# PowerReplayUSB.net
KiCad netlist of a schematic drawn in EAGLE
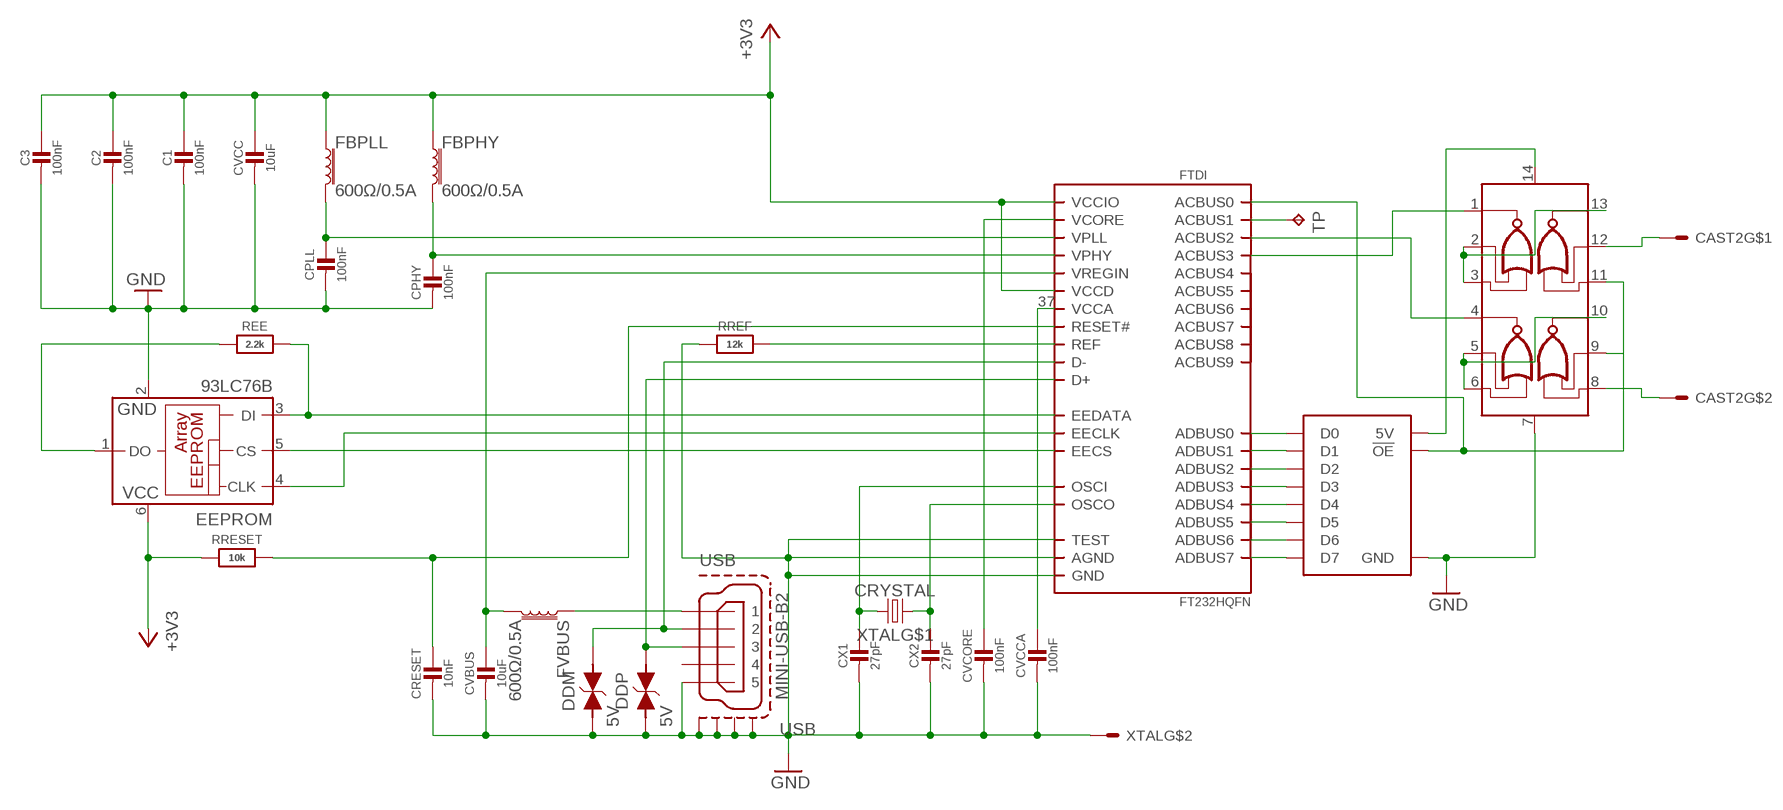
[diagram p0: schematic, sheet 1]

(export (version "E")
  (design (tool "Eeschema 10.0.6"))
  (components
    (comp (ref "C1")
      (value "100nF")
      (footprint "eagle-import:0603")
      (libsource (lib "eagle-import") (part "CAPACITOR0603"))
    )
    (comp (ref "C2")
      (value "100nF")
      (footprint "eagle-import:0603")
      (libsource (lib "eagle-import") (part "CAPACITOR0603"))
    )
    (comp (ref "C3")
      (value "100nF")
      (footprint "eagle-import:0603")
      (libsource (lib "eagle-import") (part "CAPACITOR0603"))
    )
    (comp (ref "CAST1")
      (value "BUFFER-CASTELLATION")
      (footprint "eagle-import:BUFFER-CASTELLATION")
      (libsource (lib "eagle-import") (part "BUFFER-CASTELLATION"))
    )
    (comp (ref "CAST2")
      (value "PLA-CASTELLATION")
      (footprint "eagle-import:PLA-CASTELLATION")
      (libsource (lib "eagle-import") (part "PLA-CASTELLATION"))
    )
    (comp (ref "CPHY")
      (value "100nF")
      (footprint "eagle-import:0603")
      (libsource (lib "eagle-import") (part "CAPACITOR0603"))
    )
    (comp (ref "CPLL")
      (value "100nF")
      (footprint "eagle-import:0603")
      (libsource (lib "eagle-import") (part "CAPACITOR0603"))
    )
    (comp (ref "CRESET")
      (value "10nF")
      (footprint "eagle-import:0603")
      (libsource (lib "eagle-import") (part "CAPACITOR0603"))
    )
    (comp (ref "CVBUS")
      (value "10uF")
      (footprint "eagle-import:1206")
      (libsource (lib "eagle-import") (part "CAPACITOR1206"))
    )
    (comp (ref "CVCC")
      (value "10uF")
      (footprint "eagle-import:1206")
      (libsource (lib "eagle-import") (part "CAPACITOR1206"))
    )
    (comp (ref "CVCCA")
      (value "100nF")
      (footprint "eagle-import:0603")
      (libsource (lib "eagle-import") (part "CAPACITOR0603"))
    )
    (comp (ref "CVCORE")
      (value "100nF")
      (footprint "eagle-import:0603")
      (libsource (lib "eagle-import") (part "CAPACITOR0603"))
    )
    (comp (ref "CX1")
      (value "27pF")
      (footprint "eagle-import:0402")
      (libsource (lib "eagle-import") (part "CAPACITOR0402"))
    )
    (comp (ref "CX2")
      (value "27pF")
      (footprint "eagle-import:0402")
      (libsource (lib "eagle-import") (part "CAPACITOR0402"))
    )
    (comp (ref "DDM")
      (value "5V")
      (footprint "eagle-import:WE-VE_0603")
      (libsource (lib "eagle-import") (part "WE-VE_0603_82356050050"))
    )
    (comp (ref "DDP")
      (value "5V")
      (footprint "eagle-import:WE-VE_0603")
      (libsource (lib "eagle-import") (part "WE-VE_0603_82356050050"))
    )
    (comp (ref "EEPROM")
      (value "93LC76B")
      (footprint "eagle-import:SOT23-6")
      (fields (field (name "MF") "MICROCHIP") (field (name "MPN") "93LC76BT-I/OT"))
      (libsource (lib "eagle-import") (part "9376?BLC"))
    )
    (comp (ref "FBPHY")
      (value "600Ω/0.5A")
      (footprint "eagle-import:0603")
      (libsource (lib "eagle-import") (part "FERRITE_BEAD-0603"))
    )
    (comp (ref "FBPLL")
      (value "600Ω/0.5A")
      (footprint "eagle-import:0603")
      (libsource (lib "eagle-import") (part "FERRITE_BEAD-0603"))
    )
    (comp (ref "FTDI")
      (value "FT232HQFN")
      (footprint "eagle-import:QFN48_8MM")
      (libsource (lib "eagle-import") (part "FT232HQFN"))
    )
    (comp (ref "FVBUS")
      (value "600Ω/0.5A")
      (footprint "eagle-import:0603")
      (libsource (lib "eagle-import") (part "FERRITE_BEAD-0603"))
    )
    (comp (ref "GATES")
      (value "7402TSSOP14")
      (footprint "eagle-import:TSSOP14-RU")
      (libsource (lib "eagle-import") (part "7402TSSOP14"))
    )
    (comp (ref "REE")
      (value "2.2k")
      (footprint "eagle-import:0603")
      (libsource (lib "eagle-import") (part "RESISTOR0603"))
    )
    (comp (ref "RREF")
      (value "12k")
      (footprint "eagle-import:0603")
      (libsource (lib "eagle-import") (part "RESISTOR0603"))
    )
    (comp (ref "RRESET")
      (value "10k")
      (footprint "eagle-import:0603")
      (libsource (lib "eagle-import") (part "RESISTOR0603"))
    )
    (comp (ref "TP") (value "TP") (footprint "eagle-import:TP") (libsource (lib "eagle-import") (part "TP")))
    (comp (ref "USB")
      (value "MINI-USB-B2")
      (footprint "eagle-import:MINI-USB-B-2")
      (libsource (lib "eagle-import") (part "MINI-USB-B2"))
    )
    (comp (ref "XTAL")
      (value "CRYSTAL")
      (footprint "eagle-import:SMD3225-4P")
      (libsource (lib "eagle-import") (part "CRYSTAL"))
    )
  )
  (nets
    (net (code "1") (name "+3V3") (class "Default")
      (node (ref "C1") (pin "1") (pinfunction "1_1") (pintype "passive"))
      (node (ref "C2") (pin "1") (pinfunction "1_1") (pintype "passive"))
      (node (ref "C3") (pin "1") (pinfunction "1_1") (pintype "passive"))
      (node (ref "CVCC") (pin "1") (pinfunction "1_1") (pintype "passive"))
      (node (ref "EEPROM") (pin "6") (pinfunction "VCC_6") (pintype "power_in"))
      (node (ref "FBPHY") (pin "1") (pinfunction "1_1") (pintype "passive"))
      (node (ref "FBPLL") (pin "1") (pinfunction "1_1") (pintype "passive"))
      (node (ref "FTDI") (pin "12") (pinfunction "VCCIO_12") (pintype "bidirectional"))
      (node (ref "FTDI") (pin "24") (pinfunction "VCCIO_24") (pintype "bidirectional"))
      (node (ref "FTDI") (pin "39") (pinfunction "VCCD_39") (pintype "bidirectional"))
      (node (ref "FTDI") (pin "46") (pinfunction "VCCIO_46") (pintype "bidirectional"))
      (node (ref "RRESET") (pin "1") (pinfunction "1_1") (pintype "passive"))
    )
    (net (code "2") (name "GND") (class "Default")
      (node (ref "C1") (pin "2") (pinfunction "2_2") (pintype "passive"))
      (node (ref "C2") (pin "2") (pinfunction "2_2") (pintype "passive"))
      (node (ref "C3") (pin "2") (pinfunction "2_2") (pintype "passive"))
      (node (ref "CAST1") (pin "P$9") (pinfunction "GND_P$9") (pintype "input"))
      (node (ref "CPHY") (pin "2") (pinfunction "2_2") (pintype "passive"))
      (node (ref "CPLL") (pin "2") (pinfunction "2_2") (pintype "passive"))
      (node (ref "CRESET") (pin "2") (pinfunction "2_2") (pintype "passive"))
      (node (ref "CVBUS") (pin "2") (pinfunction "2_2") (pintype "passive"))
      (node (ref "CVCC") (pin "2") (pinfunction "2_2") (pintype "passive"))
      (node (ref "CVCCA") (pin "2") (pinfunction "2_2") (pintype "passive"))
      (node (ref "CVCORE") (pin "2") (pinfunction "2_2") (pintype "passive"))
      (node (ref "CX1") (pin "2") (pinfunction "2_2") (pintype "passive"))
      (node (ref "CX2") (pin "2") (pinfunction "2_2") (pintype "passive"))
      (node (ref "DDM") (pin "2") (pinfunction "2_2") (pintype "passive"))
      (node (ref "DDP") (pin "2") (pinfunction "2_2") (pintype "passive"))
      (node (ref "EEPROM") (pin "2") (pinfunction "GND_2") (pintype "power_in"))
      (node (ref "FTDI") (pin "10") (pinfunction "GND_10") (pintype "bidirectional"))
      (node (ref "FTDI") (pin "11") (pinfunction "GND_11") (pintype "bidirectional"))
      (node (ref "FTDI") (pin "22") (pinfunction "GND_22") (pintype "bidirectional"))
      (node (ref "FTDI") (pin "23") (pinfunction "GND_23") (pintype "bidirectional"))
      (node (ref "FTDI") (pin "35") (pinfunction "GND_35") (pintype "bidirectional"))
      (node (ref "FTDI") (pin "36") (pinfunction "GND_36") (pintype "bidirectional"))
      (node (ref "FTDI") (pin "4") (pinfunction "AGND_4") (pintype "bidirectional"))
      (node (ref "FTDI") (pin "41") (pinfunction "AGND_41") (pintype "bidirectional"))
      (node (ref "FTDI") (pin "42") (pinfunction "TEST_42") (pintype "bidirectional"))
      (node (ref "FTDI") (pin "47") (pinfunction "GND_47") (pintype "bidirectional"))
      (node (ref "FTDI") (pin "48") (pinfunction "GND_48") (pintype "bidirectional"))
      (node (ref "FTDI") (pin "9") (pinfunction "AGND_9") (pintype "bidirectional"))
      (node (ref "FTDI") (pin "THERMAL") (pinfunction "GND_THERMAL") (pintype "bidirectional"))
      (node (ref "GATES") (pin "7") (pinfunction "P$7_7") (pintype "bidirectional"))
      (node (ref "RREF") (pin "1") (pinfunction "1_1") (pintype "passive"))
      (node (ref "USB") (pin "P$5") (pinfunction "5_P$5") (pintype "input"))
      (node (ref "USB") (pin "P$6") (pinfunction "S1_P$6") (pintype "passive"))
      (node (ref "USB") (pin "P$7") (pinfunction "S2_P$7") (pintype "passive"))
      (node (ref "USB") (pin "P$8") (pinfunction "S3_P$8") (pintype "passive"))
      (node (ref "USB") (pin "P$9") (pinfunction "S4_P$9") (pintype "passive"))
      (node (ref "XTAL") (pin "P$2") (pinfunction "S_P$2") (pintype "passive"))
      (node (ref "XTAL") (pin "P$4") (pinfunction "S_P$4") (pintype "passive"))
    )
    (net (code "3") (name "Net-(CAST1-5V)") (class "Default")
      (node (ref "CAST1") (pin "P$11") (pinfunction "5V_P$11") (pintype "input"))
      (node (ref "GATES") (pin "14") (pinfunction "P$14_14") (pintype "bidirectional"))
    )
    (net (code "4") (name "Net-(CAST1-D0)") (class "Default")
      (node (ref "CAST1") (pin "P$1") (pinfunction "D0_P$1") (pintype "input"))
      (node (ref "FTDI") (pin "13") (pinfunction "ADBUS0_13") (pintype "bidirectional"))
    )
    (net (code "5") (name "Net-(CAST1-D1)") (class "Default")
      (node (ref "CAST1") (pin "P$2") (pinfunction "D1_P$2") (pintype "input"))
      (node (ref "FTDI") (pin "14") (pinfunction "ADBUS1_14") (pintype "bidirectional"))
    )
    (net (code "6") (name "Net-(CAST1-D2)") (class "Default")
      (node (ref "CAST1") (pin "P$3") (pinfunction "D2_P$3") (pintype "input"))
      (node (ref "FTDI") (pin "15") (pinfunction "ADBUS2_15") (pintype "bidirectional"))
    )
    (net (code "7") (name "Net-(CAST1-D3)") (class "Default")
      (node (ref "CAST1") (pin "P$4") (pinfunction "D3_P$4") (pintype "input"))
      (node (ref "FTDI") (pin "16") (pinfunction "ADBUS3_16") (pintype "bidirectional"))
    )
    (net (code "8") (name "Net-(CAST1-D4)") (class "Default")
      (node (ref "CAST1") (pin "P$5") (pinfunction "D4_P$5") (pintype "input"))
      (node (ref "FTDI") (pin "17") (pinfunction "ADBUS4_17") (pintype "bidirectional"))
    )
    (net (code "9") (name "Net-(CAST1-D5)") (class "Default")
      (node (ref "CAST1") (pin "P$6") (pinfunction "D5_P$6") (pintype "input"))
      (node (ref "FTDI") (pin "18") (pinfunction "ADBUS5_18") (pintype "bidirectional"))
    )
    (net (code "10") (name "Net-(CAST1-D6)") (class "Default")
      (node (ref "CAST1") (pin "P$7") (pinfunction "D6_P$7") (pintype "input"))
      (node (ref "FTDI") (pin "19") (pinfunction "ADBUS6_19") (pintype "bidirectional"))
    )
    (net (code "11") (name "Net-(CAST1-D7)") (class "Default")
      (node (ref "CAST1") (pin "P$8") (pinfunction "D7_P$8") (pintype "input"))
      (node (ref "FTDI") (pin "20") (pinfunction "ADBUS7_20") (pintype "bidirectional"))
    )
    (net (code "12") (name "Net-(CAST1-~{OE})") (class "Default")
      (node (ref "CAST1") (pin "P$10") (pinfunction "~{OE}_P$10") (pintype "input"))
      (node (ref "FTDI") (pin "21") (pinfunction "ACBUS0_21") (pintype "bidirectional"))
      (node (ref "GATES") (pin "11") (pinfunction "P$11_11") (pintype "bidirectional"))
      (node (ref "GATES") (pin "9") (pinfunction "P$9_9") (pintype "bidirectional"))
    )
    (net (code "13") (name "Net-(CAST2A-S)") (class "Default")
      (node (ref "CAST2") (pin "P$1") (pinfunction "S_P$1") (pintype "passive"))
      (node (ref "GATES") (pin "12") (pinfunction "P$12_12") (pintype "bidirectional"))
    )
    (net (code "14") (name "Net-(CAST2B-S)") (class "Default")
      (node (ref "CAST2") (pin "P$2") (pinfunction "S_P$2") (pintype "passive"))
      (node (ref "GATES") (pin "8") (pinfunction "P$8_8") (pintype "bidirectional"))
    )
    (net (code "15") (name "Net-(EEPROM-CLK)") (class "Default")
      (node (ref "EEPROM") (pin "4") (pinfunction "CLK_4") (pintype "input"))
      (node (ref "FTDI") (pin "44") (pinfunction "EECLK_44") (pintype "bidirectional"))
    )
    (net (code "16") (name "Net-(EEPROM-CS)") (class "Default")
      (node (ref "EEPROM") (pin "5") (pinfunction "CS_5") (pintype "input"))
      (node (ref "FTDI") (pin "45") (pinfunction "EECS_45") (pintype "bidirectional"))
    )
    (net (code "17") (name "Net-(EEPROM-DI)") (class "Default")
      (node (ref "EEPROM") (pin "3") (pinfunction "DI_3") (pintype "input"))
      (node (ref "FTDI") (pin "43") (pinfunction "EEDATA_43") (pintype "bidirectional"))
      (node (ref "REE") (pin "2") (pinfunction "2_2") (pintype "passive"))
    )
    (net (code "18") (name "Net-(EEPROM-DO)") (class "Default")
      (node (ref "EEPROM") (pin "1") (pinfunction "DO_1") (pintype "tri_state"))
      (node (ref "REE") (pin "1") (pinfunction "1_1") (pintype "passive"))
    )
    (net (code "19") (name "Net-(FTDI-ACBUS1)") (class "Default")
      (node (ref "FTDI") (pin "25") (pinfunction "ACBUS1_25") (pintype "bidirectional"))
      (node (ref "TP") (pin "P$1") (pinfunction "TP_P$1") (pintype "input"))
    )
    (net (code "20") (name "Net-(FTDI-ACBUS2)") (class "Default")
      (node (ref "FTDI") (pin "26") (pinfunction "ACBUS2_26") (pintype "bidirectional"))
      (node (ref "GATES") (pin "4") (pinfunction "P$4_4") (pintype "bidirectional"))
    )
    (net (code "21") (name "Net-(FTDI-ACBUS3)") (class "Default")
      (node (ref "FTDI") (pin "27") (pinfunction "ACBUS3_27") (pintype "bidirectional"))
      (node (ref "GATES") (pin "1") (pinfunction "P$1_1") (pintype "bidirectional"))
    )
    (net (code "22") (name "Net-(FTDI-D+)") (class "Default")
      (node (ref "DDP") (pin "1") (pinfunction "1_1") (pintype "passive"))
      (node (ref "FTDI") (pin "7") (pinfunction "D+_7") (pintype "bidirectional"))
      (node (ref "USB") (pin "P$3") (pinfunction "3_P$3") (pintype "input"))
    )
    (net (code "23") (name "Net-(FTDI-D-)") (class "Default")
      (node (ref "DDM") (pin "1") (pinfunction "1_1") (pintype "passive"))
      (node (ref "FTDI") (pin "6") (pinfunction "D-_6") (pintype "bidirectional"))
      (node (ref "USB") (pin "P$2") (pinfunction "2_P$2") (pintype "input"))
    )
    (net (code "24") (name "Net-(FTDI-OSCI)") (class "Default")
      (node (ref "CX1") (pin "1") (pinfunction "1_1") (pintype "passive"))
      (node (ref "FTDI") (pin "1") (pinfunction "OSCI_1") (pintype "bidirectional"))
      (node (ref "XTAL") (pin "P$1") (pinfunction "X1_P$1") (pintype "passive"))
    )
    (net (code "25") (name "Net-(FTDI-OSCO)") (class "Default")
      (node (ref "CX2") (pin "1") (pinfunction "1_1") (pintype "passive"))
      (node (ref "FTDI") (pin "2") (pinfunction "OSCO_2") (pintype "bidirectional"))
      (node (ref "XTAL") (pin "P$3") (pinfunction "X2_P$3") (pintype "passive"))
    )
    (net (code "26") (name "Net-(FTDI-REF)") (class "Default")
      (node (ref "FTDI") (pin "5") (pinfunction "REF_5") (pintype "bidirectional"))
      (node (ref "RREF") (pin "2") (pinfunction "2_2") (pintype "passive"))
    )
    (net (code "27") (name "Net-(FTDI-RESET#)") (class "Default")
      (node (ref "CRESET") (pin "1") (pinfunction "1_1") (pintype "passive"))
      (node (ref "FTDI") (pin "34") (pinfunction "RESET#_34") (pintype "bidirectional"))
      (node (ref "RRESET") (pin "2") (pinfunction "2_2") (pintype "passive"))
    )
    (net (code "28") (name "Net-(FTDI-VCCA)") (class "Default")
      (node (ref "CVCCA") (pin "1") (pinfunction "1_1") (pintype "passive"))
      (node (ref "FTDI") (pin "37") (pinfunction "VCCA_37") (pintype "bidirectional"))
    )
    (net (code "29") (name "Net-(FTDI-VCORE)") (class "Default")
      (node (ref "CVCORE") (pin "1") (pinfunction "1_1") (pintype "passive"))
      (node (ref "FTDI") (pin "38") (pinfunction "VCORE_38") (pintype "bidirectional"))
    )
    (net (code "30") (name "Net-(FTDI-VPHY)") (class "Default")
      (node (ref "CPHY") (pin "1") (pinfunction "1_1") (pintype "passive"))
      (node (ref "FBPHY") (pin "2") (pinfunction "2_2") (pintype "passive"))
      (node (ref "FTDI") (pin "3") (pinfunction "VPHY_3") (pintype "bidirectional"))
    )
    (net (code "31") (name "Net-(FTDI-VPLL)") (class "Default")
      (node (ref "CPLL") (pin "1") (pinfunction "1_1") (pintype "passive"))
      (node (ref "FBPLL") (pin "2") (pinfunction "2_2") (pintype "passive"))
      (node (ref "FTDI") (pin "8") (pinfunction "VPLL_8") (pintype "bidirectional"))
    )
    (net (code "32") (name "Net-(FTDI-VREGIN)") (class "Default")
      (node (ref "CVBUS") (pin "1") (pinfunction "1_1") (pintype "passive"))
      (node (ref "FTDI") (pin "40") (pinfunction "VREGIN_40") (pintype "bidirectional"))
      (node (ref "FVBUS") (pin "2") (pinfunction "2_2") (pintype "passive"))
    )
    (net (code "33") (name "Net-(GATES-P$10)") (class "Default")
      (node (ref "GATES") (pin "10") (pinfunction "P$10_10") (pintype "bidirectional"))
      (node (ref "GATES") (pin "5") (pinfunction "P$5_5") (pintype "bidirectional"))
      (node (ref "GATES") (pin "6") (pinfunction "P$6_6") (pintype "bidirectional"))
    )
    (net (code "34") (name "Net-(GATES-P$13)") (class "Default")
      (node (ref "GATES") (pin "13") (pinfunction "P$13_13") (pintype "bidirectional"))
      (node (ref "GATES") (pin "2") (pinfunction "P$2_2") (pintype "bidirectional"))
      (node (ref "GATES") (pin "3") (pinfunction "P$3_3") (pintype "bidirectional"))
    )
    (net (code "35") (name "Net-(USB-1)") (class "Default")
      (node (ref "FVBUS") (pin "1") (pinfunction "1_1") (pintype "passive"))
      (node (ref "USB") (pin "P$1") (pinfunction "1_P$1") (pintype "input"))
    )
    (net (code "36") (name "unconnected-(FTDI-ACBUS4-Pad28)") (class "Default")
      (node (ref "FTDI") (pin "28") (pinfunction "ACBUS4_28") (pintype "bidirectional"))
    )
    (net (code "37") (name "unconnected-(FTDI-ACBUS5-Pad29)") (class "Default")
      (node (ref "FTDI") (pin "29") (pinfunction "ACBUS5_29") (pintype "bidirectional"))
    )
    (net (code "38") (name "unconnected-(FTDI-ACBUS6-Pad30)") (class "Default")
      (node (ref "FTDI") (pin "30") (pinfunction "ACBUS6_30") (pintype "bidirectional"))
    )
    (net (code "39") (name "unconnected-(FTDI-ACBUS7-Pad31)") (class "Default")
      (node (ref "FTDI") (pin "31") (pinfunction "ACBUS7_31") (pintype "bidirectional"))
    )
    (net (code "40") (name "unconnected-(FTDI-ACBUS8-Pad32)") (class "Default")
      (node (ref "FTDI") (pin "32") (pinfunction "ACBUS8_32") (pintype "bidirectional"))
    )
    (net (code "41") (name "unconnected-(FTDI-ACBUS9-Pad33)") (class "Default")
      (node (ref "FTDI") (pin "33") (pinfunction "ACBUS9_33") (pintype "bidirectional"))
    )
    (net (code "42") (name "unconnected-(USB-4-PadP$4)") (class "Default")
      (node (ref "USB") (pin "P$4") (pinfunction "4_P$4") (pintype "input"))
    )
  )
)
